# K13-01.net
KiCad netlist of a schematic drawn in Altium Designer
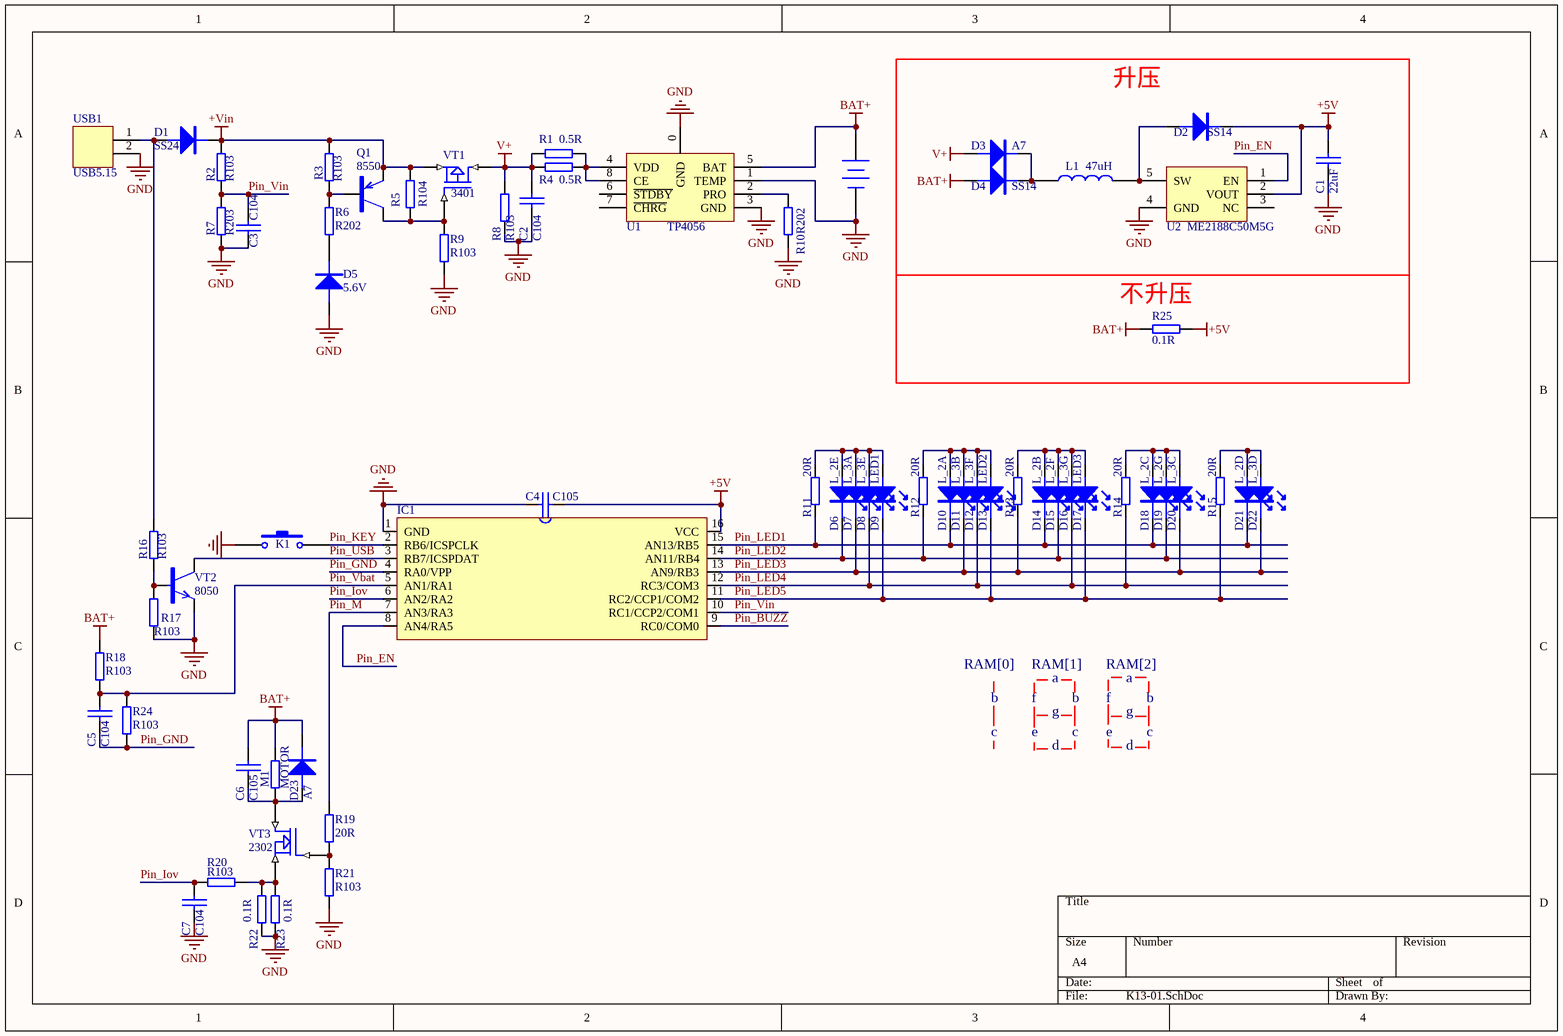
[diagram p0: K13-01.SchDoc]

(export (version "E")
  (design (tool "Eeschema 10.0.6"))
  (components
    (comp (ref "BT1")
      (value "Battery")
      (footprint "BAT")
      (fields (field (name "PUBLISHER") "Altium Limited"))
      (libsource (lib "altium-import") (part "root_3_Battery_"))
    )
    (comp (ref "C1") (value "22uF") (footprint "1206") (libsource (lib "altium-import") (part "root_0_CAP_")))
    (comp (ref "C2") (value "C104") (footprint "0603") (libsource (lib "altium-import") (part "root_2_CAP_")))
    (comp (ref "C3") (value "C104") (footprint "0603") (libsource (lib "altium-import") (part "root_2_CAP_")))
    (comp (ref "C4")
      (value "C105")
      (footprint "0805N")
      (libsource (lib "altium-import") (part "root_3_CAP_"))
    )
    (comp (ref "C5") (value "C104") (footprint "0603") (libsource (lib "altium-import") (part "root_2_CAP_")))
    (comp (ref "C6")
      (value "C105")
      (footprint "0805N")
      (libsource (lib "altium-import") (part "root_2_CAP_"))
    )
    (comp (ref "C7") (value "C104") (footprint "0603") (libsource (lib "altium-import") (part "root_2_CAP_")))
    (comp (ref "D1")
      (value "SS24")
      (footprint "DO-214AC")
      (libsource (lib "altium-import") (part "root_0_DIODE_"))
    )
    (comp (ref "D2")
      (value "SS14")
      (footprint "DO-214AC")
      (libsource (lib "altium-import") (part "root_0_DIODE_"))
    )
    (comp (ref "D3")
      (value "A7")
      (footprint "DO-214AC")
      (libsource (lib "altium-import") (part "root_0_DIODE_"))
    )
    (comp (ref "D4")
      (value "SS14")
      (footprint "DO-214AC")
      (libsource (lib "altium-import") (part "root_0_DIODE_"))
    )
    (comp (ref "D5")
      (value "5.6V")
      (footprint "4148")
      (libsource (lib "altium-import") (part "root_1_DIODE_"))
    )
    (comp (ref "D6")
      (value "L_2E")
      (footprint "LED0603")
      (libsource (lib "altium-import") (part "root_3_LED_"))
    )
    (comp (ref "D7")
      (value "L_3A")
      (footprint "LED0603")
      (libsource (lib "altium-import") (part "root_3_LED_"))
    )
    (comp (ref "D8")
      (value "L_3E")
      (footprint "LED0603")
      (libsource (lib "altium-import") (part "root_3_LED_"))
    )
    (comp (ref "D9")
      (value "LED1")
      (footprint "LED0603")
      (libsource (lib "altium-import") (part "root_3_LED_"))
    )
    (comp (ref "D10")
      (value "L_2A")
      (footprint "LED0603")
      (libsource (lib "altium-import") (part "root_3_LED_"))
    )
    (comp (ref "D11")
      (value "L_3B")
      (footprint "LED0603")
      (libsource (lib "altium-import") (part "root_3_LED_"))
    )
    (comp (ref "D12")
      (value "L_3F")
      (footprint "LED0603")
      (libsource (lib "altium-import") (part "root_3_LED_"))
    )
    (comp (ref "D13")
      (value "LED2")
      (footprint "LED0603")
      (libsource (lib "altium-import") (part "root_3_LED_"))
    )
    (comp (ref "D14")
      (value "L_2B")
      (footprint "LED0603")
      (libsource (lib "altium-import") (part "root_3_LED_"))
    )
    (comp (ref "D15")
      (value "L_2F")
      (footprint "LED0603")
      (libsource (lib "altium-import") (part "root_3_LED_"))
    )
    (comp (ref "D16")
      (value "L_3G")
      (footprint "LED0603")
      (libsource (lib "altium-import") (part "root_3_LED_"))
    )
    (comp (ref "D17")
      (value "LED3")
      (footprint "LED0603")
      (libsource (lib "altium-import") (part "root_3_LED_"))
    )
    (comp (ref "D18")
      (value "L_2C")
      (footprint "LED0603")
      (libsource (lib "altium-import") (part "root_3_LED_"))
    )
    (comp (ref "D19")
      (value "L_2G")
      (footprint "LED0603")
      (libsource (lib "altium-import") (part "root_3_LED_"))
    )
    (comp (ref "D20")
      (value "L_3C")
      (footprint "LED0603")
      (libsource (lib "altium-import") (part "root_3_LED_"))
    )
    (comp (ref "D21")
      (value "L_2D")
      (footprint "LED0603")
      (libsource (lib "altium-import") (part "root_3_LED_"))
    )
    (comp (ref "D22")
      (value "L_3D")
      (footprint "LED0603")
      (libsource (lib "altium-import") (part "root_3_LED_"))
    )
    (comp (ref "D23")
      (value "A7")
      (footprint "4148")
      (libsource (lib "altium-import") (part "root_1_mirrored_DIODE_"))
    )
    (comp (ref "IC1") (value "~") (footprint "SOP-16") (libsource (lib "MySCHLib") (part "MCU_1712")))
    (comp (ref "K1")
      (value "SW-PB")
      (footprint "D6_SMT")
      (fields (field (name "PUBLISHER") "Altium Limited"))
      (libsource (lib "altium-import") (part "root_0_SW-PB_"))
    )
    (comp (ref "L1")
      (value "47uH")
      (footprint "CD4X")
      (description "1.5A以上")
      (libsource (lib "YF SCHlib V1.00") (part "L"))
    )
    (comp (ref "M1")
      (value "MOTOR")
      (footprint "bat")
      (libsource (lib "altium-import") (part "root_1_RES2_"))
    )
    (comp (ref "Q1") (value "8550") (footprint "sot-23") (libsource (lib "MySCHLib") (part "8550-SMT")))
    (comp (ref "R1")
      (value "0.5R")
      (footprint "1206")
      (libsource (lib "altium-import") (part "root_0_RES2_"))
    )
    (comp (ref "R2")
      (value "R103")
      (footprint "0603")
      (libsource (lib "altium-import") (part "root_3_RES2_"))
    )
    (comp (ref "R3")
      (value "R103")
      (footprint "0603")
      (libsource (lib "altium-import") (part "root_3_RES2_"))
    )
    (comp (ref "R4")
      (value "0.5R")
      (footprint "1206")
      (libsource (lib "altium-import") (part "root_0_RES2_"))
    )
    (comp (ref "R5")
      (value "R104")
      (footprint "0603")
      (libsource (lib "altium-import") (part "root_1_RES2_"))
    )
    (comp (ref "R6")
      (value "R202")
      (footprint "0603")
      (libsource (lib "altium-import") (part "root_1_RES2_"))
    )
    (comp (ref "R7")
      (value "R203")
      (footprint "0603")
      (libsource (lib "altium-import") (part "root_3_RES2_"))
    )
    (comp (ref "R8")
      (value "R103")
      (footprint "0603")
      (libsource (lib "altium-import") (part "root_3_RES2_"))
    )
    (comp (ref "R9")
      (value "R103")
      (footprint "0603")
      (libsource (lib "altium-import") (part "root_1_RES2_"))
    )
    (comp (ref "R10")
      (value "R202")
      (footprint "0603")
      (libsource (lib "altium-import") (part "root_3_RES2_"))
    )
    (comp (ref "R11")
      (value "20R")
      (footprint "0603")
      (libsource (lib "altium-import") (part "root_1_mirrored_RES2_"))
    )
    (comp (ref "R12")
      (value "20R")
      (footprint "0603")
      (libsource (lib "altium-import") (part "root_1_mirrored_RES2_"))
    )
    (comp (ref "R13")
      (value "20R")
      (footprint "0603")
      (libsource (lib "altium-import") (part "root_3_mirrored_RES2_"))
    )
    (comp (ref "R14")
      (value "20R")
      (footprint "0603")
      (libsource (lib "altium-import") (part "root_1_mirrored_RES2_"))
    )
    (comp (ref "R15")
      (value "20R")
      (footprint "0603")
      (libsource (lib "altium-import") (part "root_1_mirrored_RES2_"))
    )
    (comp (ref "R16")
      (value "R103")
      (footprint "0603")
      (libsource (lib "altium-import") (part "root_1_RES2_"))
    )
    (comp (ref "R17")
      (value "R103")
      (footprint "0603")
      (libsource (lib "altium-import") (part "root_1_RES2_"))
    )
    (comp (ref "R18")
      (value "R103")
      (footprint "0603")
      (libsource (lib "altium-import") (part "root_1_mirrored_RES2_"))
    )
    (comp (ref "R19")
      (value "20R")
      (footprint "0603")
      (libsource (lib "altium-import") (part "root_1_mirrored_RES2_"))
    )
    (comp (ref "R20")
      (value "R103")
      (footprint "0603")
      (libsource (lib "altium-import") (part "root_0_RES2_"))
    )
    (comp (ref "R21")
      (value "R103")
      (footprint "0603")
      (libsource (lib "altium-import") (part "root_3_mirrored_RES2_"))
    )
    (comp (ref "R22")
      (value "0.1R")
      (footprint "1206")
      (libsource (lib "altium-import") (part "root_1_RES2_"))
    )
    (comp (ref "R23")
      (value "0.1R")
      (footprint "1206")
      (libsource (lib "altium-import") (part "root_1_RES2_"))
    )
    (comp (ref "R24")
      (value "R103")
      (footprint "0603")
      (libsource (lib "altium-import") (part "root_3_mirrored_RES2_"))
    )
    (comp (ref "R25")
      (value "0.1R")
      (footprint "1206")
      (libsource (lib "altium-import") (part "root_2_mirrored_RES2_"))
    )
    (comp (ref "U1") (value "TP4056") (footprint "ESOP-8") (libsource (lib "MySCHLib") (part "TP4056")))
    (comp (ref "U2")
      (value "ME2188C50M5G")
      (footprint "SOT-23-5")
      (libsource (lib "MySCHLib") (part "TP5303"))
    )
    (comp (ref "USB1")
      (value "USB5.15")
      (footprint "BAT")
      (libsource (lib "altium-import") (part "root_0_USB2_"))
    )
    (comp (ref "VT1") (value "3401") (footprint "SOT-23") (libsource (lib "MySCHLib") (part "MOSFET P")))
    (comp (ref "VT2") (value "8050") (footprint "SOT-23") (libsource (lib "MySCHLib") (part "8050-SMT")))
    (comp (ref "VT3")
      (value "2302")
      (footprint "sot-23")
      (libsource (lib "altium-import") (part "root_0_mirrored_MOSFET N_"))
    )
  )
  (nets
    (net (code "1") (name "+5V") (class "Default")
      (node (ref "C1") (pin "1") (pinfunction "1_1") (pintype "passive"))
      (node (ref "C4") (pin "1") (pinfunction "1_1") (pintype "passive"))
      (node (ref "D2") (pin "2") (pinfunction "K_2") (pintype "passive"))
      (node (ref "IC1") (pin "16") (pinfunction "VCC_16") (pintype "passive"))
      (node (ref "R25") (pin "2") (pinfunction "2_2") (pintype "passive"))
      (node (ref "U2") (pin "2") (pinfunction "VOUT_2") (pintype "passive"))
    )
    (net (code "2") (name "+Vin") (class "Default")
      (node (ref "D1") (pin "2") (pinfunction "K_2") (pintype "passive"))
      (node (ref "Q1") (pin "2") (pinfunction "E_2") (pintype "passive"))
      (node (ref "R2") (pin "1") (pinfunction "1_1") (pintype "passive"))
      (node (ref "R3") (pin "1") (pinfunction "1_1") (pintype "passive"))
      (node (ref "R5") (pin "2") (pinfunction "2_2") (pintype "passive"))
      (node (ref "VT1") (pin "2") (pinfunction "S_2") (pintype "input"))
    )
    (net (code "3") (name "/Pin_BUZZ") (class "Default")
      (node (ref "IC1") (pin "9") (pinfunction "RC0/COM0_9") (pintype "passive"))
    )
    (net (code "4") (name "/Pin_EN") (class "Default")
      (node (ref "IC1") (pin "8") (pinfunction "AN4/RA5_8") (pintype "passive"))
      (node (ref "U2") (pin "1") (pinfunction "EN_1") (pintype "passive"))
    )
    (net (code "5") (name "/Pin_GND") (class "Default")
      (node (ref "C5") (pin "1") (pinfunction "1_1") (pintype "passive"))
      (node (ref "IC1") (pin "4") (pinfunction "RA0/VPP_4") (pintype "passive"))
      (node (ref "R24") (pin "2") (pinfunction "2_2") (pintype "passive"))
    )
    (net (code "6") (name "/Pin_Iov") (class "Default")
      (node (ref "C7") (pin "2") (pinfunction "2_2") (pintype "passive"))
      (node (ref "IC1") (pin "6") (pinfunction "AN2/RA2_6") (pintype "passive"))
      (node (ref "R20") (pin "1") (pinfunction "1_1") (pintype "passive"))
    )
    (net (code "7") (name "/Pin_KEY") (class "Default")
      (node (ref "IC1") (pin "2") (pinfunction "RB6/ICSPCLK_2") (pintype "passive"))
      (node (ref "K1") (pin "2") (pinfunction "2_2") (pintype "passive"))
    )
    (net (code "8") (name "/Pin_LED1") (class "Default")
      (node (ref "D10") (pin "2") (pinfunction "2_2") (pintype "passive"))
      (node (ref "D14") (pin "2") (pinfunction "2_2") (pintype "passive"))
      (node (ref "D18") (pin "2") (pinfunction "2_2") (pintype "passive"))
      (node (ref "D21") (pin "2") (pinfunction "2_2") (pintype "passive"))
      (node (ref "IC1") (pin "15") (pinfunction "AN13/RB5_15") (pintype "passive"))
      (node (ref "R11") (pin "1") (pinfunction "1_1") (pintype "passive"))
    )
    (net (code "9") (name "/Pin_LED2") (class "Default")
      (node (ref "D15") (pin "2") (pinfunction "2_2") (pintype "passive"))
      (node (ref "D19") (pin "2") (pinfunction "2_2") (pintype "passive"))
      (node (ref "D6") (pin "2") (pinfunction "2_2") (pintype "passive"))
      (node (ref "IC1") (pin "14") (pinfunction "AN11/RB4_14") (pintype "passive"))
      (node (ref "R12") (pin "1") (pinfunction "1_1") (pintype "passive"))
    )
    (net (code "10") (name "/Pin_LED3") (class "Default")
      (node (ref "D11") (pin "2") (pinfunction "2_2") (pintype "passive"))
      (node (ref "D20") (pin "2") (pinfunction "2_2") (pintype "passive"))
      (node (ref "D22") (pin "2") (pinfunction "2_2") (pintype "passive"))
      (node (ref "D7") (pin "2") (pinfunction "2_2") (pintype "passive"))
      (node (ref "IC1") (pin "13") (pinfunction "AN9/RB3_13") (pintype "passive"))
      (node (ref "R13") (pin "2") (pinfunction "2_2") (pintype "passive"))
    )
    (net (code "11") (name "/Pin_LED4") (class "Default")
      (node (ref "D12") (pin "2") (pinfunction "2_2") (pintype "passive"))
      (node (ref "D16") (pin "2") (pinfunction "2_2") (pintype "passive"))
      (node (ref "D8") (pin "2") (pinfunction "2_2") (pintype "passive"))
      (node (ref "IC1") (pin "12") (pinfunction "RC3/COM3_12") (pintype "passive"))
      (node (ref "R14") (pin "1") (pinfunction "1_1") (pintype "passive"))
    )
    (net (code "12") (name "/Pin_LED5") (class "Default")
      (node (ref "D13") (pin "2") (pinfunction "2_2") (pintype "passive"))
      (node (ref "D17") (pin "2") (pinfunction "2_2") (pintype "passive"))
      (node (ref "D9") (pin "2") (pinfunction "2_2") (pintype "passive"))
      (node (ref "IC1") (pin "11") (pinfunction "RC2/CCP1/COM2_11") (pintype "passive"))
      (node (ref "R15") (pin "1") (pinfunction "1_1") (pintype "passive"))
    )
    (net (code "13") (name "/Pin_M") (class "Default")
      (node (ref "IC1") (pin "7") (pinfunction "AN3/RA3_7") (pintype "passive"))
      (node (ref "R19") (pin "2") (pinfunction "2_2") (pintype "passive"))
    )
    (net (code "14") (name "/Pin_USB") (class "Default")
      (node (ref "IC1") (pin "3") (pinfunction "RB7/ICSPDAT_3") (pintype "passive"))
      (node (ref "VT2") (pin "3") (pinfunction "C_3") (pintype "passive"))
    )
    (net (code "15") (name "/Pin_Vbat") (class "Default")
      (node (ref "C5") (pin "2") (pinfunction "2_2") (pintype "passive"))
      (node (ref "IC1") (pin "5") (pinfunction "AN1/RA1_5") (pintype "passive"))
      (node (ref "R18") (pin "1") (pinfunction "1_1") (pintype "passive"))
      (node (ref "R24") (pin "1") (pinfunction "1_1") (pintype "passive"))
    )
    (net (code "16") (name "/Pin_Vin") (class "Default")
      (node (ref "C3") (pin "2") (pinfunction "2_2") (pintype "passive"))
      (node (ref "IC1") (pin "10") (pinfunction "RC1/CCP2/COM1_10") (pintype "passive"))
      (node (ref "R2") (pin "2") (pinfunction "2_2") (pintype "passive"))
      (node (ref "R7") (pin "1") (pinfunction "1_1") (pintype "passive"))
    )
    (net (code "17") (name "BAT+") (class "Default")
      (node (ref "BT1") (pin "1") (pinfunction "+_1") (pintype "passive"))
      (node (ref "C6") (pin "2") (pinfunction "2_2") (pintype "passive"))
      (node (ref "D23") (pin "2") (pinfunction "K_2") (pintype "passive"))
      (node (ref "D4") (pin "1") (pinfunction "A_1") (pintype "passive"))
      (node (ref "M1") (pin "2") (pinfunction "2_2") (pintype "passive"))
      (node (ref "R18") (pin "2") (pinfunction "2_2") (pintype "passive"))
      (node (ref "R25") (pin "1") (pinfunction "1_1") (pintype "passive"))
      (node (ref "U1") (pin "5") (pinfunction "BAT_5") (pintype "passive"))
    )
    (net (code "18") (name "GND") (class "Default")
      (node (ref "BT1") (pin "2") (pinfunction "-_2") (pintype "passive"))
      (node (ref "C1") (pin "2") (pinfunction "2_2") (pintype "passive"))
      (node (ref "C2") (pin "1") (pinfunction "1_1") (pintype "passive"))
      (node (ref "C3") (pin "1") (pinfunction "1_1") (pintype "passive"))
      (node (ref "C4") (pin "2") (pinfunction "2_2") (pintype "passive"))
      (node (ref "C7") (pin "1") (pinfunction "1_1") (pintype "passive"))
      (node (ref "D5") (pin "1") (pinfunction "A_1") (pintype "passive"))
      (node (ref "IC1") (pin "1") (pinfunction "GND_1") (pintype "passive"))
      (node (ref "K1") (pin "1") (pinfunction "1_1") (pintype "passive"))
      (node (ref "R10") (pin "2") (pinfunction "2_2") (pintype "passive"))
      (node (ref "R17") (pin "1") (pinfunction "1_1") (pintype "passive"))
      (node (ref "R21") (pin "2") (pinfunction "2_2") (pintype "passive"))
      (node (ref "R22") (pin "1") (pinfunction "1_1") (pintype "passive"))
      (node (ref "R23") (pin "1") (pinfunction "1_1") (pintype "passive"))
      (node (ref "R7") (pin "2") (pinfunction "2_2") (pintype "passive"))
      (node (ref "R8") (pin "2") (pinfunction "2_2") (pintype "passive"))
      (node (ref "R9") (pin "1") (pinfunction "1_1") (pintype "passive"))
      (node (ref "U1") (pin "0") (pinfunction "GND_0") (pintype "passive"))
      (node (ref "U1") (pin "1") (pinfunction "TEMP_1") (pintype "passive"))
      (node (ref "U1") (pin "3") (pinfunction "GND_3") (pintype "passive"))
      (node (ref "U2") (pin "4") (pinfunction "GND_4") (pintype "passive"))
      (node (ref "USB1") (pin "2") (pinfunction "2_2") (pintype "passive"))
      (node (ref "VT2") (pin "2") (pinfunction "E_2") (pintype "passive"))
    )
    (net (code "19") (name "Net-(D1-A)") (class "Default")
      (node (ref "D1") (pin "1") (pinfunction "A_1") (pintype "passive"))
      (node (ref "R16") (pin "2") (pinfunction "2_2") (pintype "passive"))
      (node (ref "USB1") (pin "1") (pinfunction "1_1") (pintype "passive"))
    )
    (net (code "20") (name "Net-(D2-A)") (class "Default")
      (node (ref "D2") (pin "1") (pinfunction "A_1") (pintype "passive"))
      (node (ref "L1") (pin "2") (pinfunction "2_2") (pintype "passive"))
      (node (ref "U2") (pin "5") (pinfunction "SW_5") (pintype "passive"))
    )
    (net (code "21") (name "Net-(D3-K)") (class "Default")
      (node (ref "D3") (pin "2") (pinfunction "K_2") (pintype "passive"))
      (node (ref "D4") (pin "2") (pinfunction "K_2") (pintype "passive"))
      (node (ref "L1") (pin "1") (pinfunction "1_1") (pintype "passive"))
    )
    (net (code "22") (name "Net-(D5-K)") (class "Default")
      (node (ref "D5") (pin "2") (pinfunction "K_2") (pintype "passive"))
      (node (ref "R6") (pin "1") (pinfunction "1_1") (pintype "passive"))
    )
    (net (code "23") (name "Net-(D6-Pad1)") (class "Default")
      (node (ref "D6") (pin "1") (pinfunction "1_1") (pintype "passive"))
      (node (ref "D7") (pin "1") (pinfunction "1_1") (pintype "passive"))
      (node (ref "D8") (pin "1") (pinfunction "1_1") (pintype "passive"))
      (node (ref "D9") (pin "1") (pinfunction "1_1") (pintype "passive"))
      (node (ref "R11") (pin "2") (pinfunction "2_2") (pintype "passive"))
    )
    (net (code "24") (name "Net-(D10-Pad1)") (class "Default")
      (node (ref "D10") (pin "1") (pinfunction "1_1") (pintype "passive"))
      (node (ref "D11") (pin "1") (pinfunction "1_1") (pintype "passive"))
      (node (ref "D12") (pin "1") (pinfunction "1_1") (pintype "passive"))
      (node (ref "D13") (pin "1") (pinfunction "1_1") (pintype "passive"))
      (node (ref "R12") (pin "2") (pinfunction "2_2") (pintype "passive"))
    )
    (net (code "25") (name "Net-(D14-Pad1)") (class "Default")
      (node (ref "D14") (pin "1") (pinfunction "1_1") (pintype "passive"))
      (node (ref "D15") (pin "1") (pinfunction "1_1") (pintype "passive"))
      (node (ref "D16") (pin "1") (pinfunction "1_1") (pintype "passive"))
      (node (ref "D17") (pin "1") (pinfunction "1_1") (pintype "passive"))
      (node (ref "R13") (pin "1") (pinfunction "1_1") (pintype "passive"))
    )
    (net (code "26") (name "Net-(D18-Pad1)") (class "Default")
      (node (ref "D18") (pin "1") (pinfunction "1_1") (pintype "passive"))
      (node (ref "D19") (pin "1") (pinfunction "1_1") (pintype "passive"))
      (node (ref "D20") (pin "1") (pinfunction "1_1") (pintype "passive"))
      (node (ref "R14") (pin "2") (pinfunction "2_2") (pintype "passive"))
    )
    (net (code "27") (name "Net-(D21-Pad1)") (class "Default")
      (node (ref "D21") (pin "1") (pinfunction "1_1") (pintype "passive"))
      (node (ref "D22") (pin "1") (pinfunction "1_1") (pintype "passive"))
      (node (ref "R15") (pin "2") (pinfunction "2_2") (pintype "passive"))
    )
    (net (code "28") (name "Net-(D23-A)") (class "Default")
      (node (ref "C6") (pin "1") (pinfunction "1_1") (pintype "passive"))
      (node (ref "D23") (pin "1") (pinfunction "A_1") (pintype "passive"))
      (node (ref "M1") (pin "1") (pinfunction "1_1") (pintype "passive"))
      (node (ref "VT3") (pin "3") (pinfunction "D_3") (pintype "input"))
    )
    (net (code "29") (name "Net-(Q1-B)") (class "Default")
      (node (ref "Q1") (pin "1") (pinfunction "B_1") (pintype "passive"))
      (node (ref "R3") (pin "2") (pinfunction "2_2") (pintype "passive"))
      (node (ref "R6") (pin "2") (pinfunction "2_2") (pintype "passive"))
    )
    (net (code "30") (name "Net-(Q1-C)") (class "Default")
      (node (ref "Q1") (pin "3") (pinfunction "C_3") (pintype "passive"))
      (node (ref "R5") (pin "1") (pinfunction "1_1") (pintype "passive"))
      (node (ref "R9") (pin "2") (pinfunction "2_2") (pintype "passive"))
      (node (ref "VT1") (pin "1") (pinfunction "G_1") (pintype "input"))
    )
    (net (code "31") (name "Net-(U1-CE)") (class "Default")
      (node (ref "R1") (pin "2") (pinfunction "2_2") (pintype "passive"))
      (node (ref "R4") (pin "2") (pinfunction "2_2") (pintype "passive"))
      (node (ref "U1") (pin "4") (pinfunction "VDD_4") (pintype "passive"))
      (node (ref "U1") (pin "8") (pinfunction "CE_8") (pintype "passive"))
    )
    (net (code "32") (name "Net-(U1-PRO)") (class "Default")
      (node (ref "R10") (pin "1") (pinfunction "1_1") (pintype "passive"))
      (node (ref "U1") (pin "2") (pinfunction "PRO_2") (pintype "passive"))
    )
    (net (code "33") (name "Net-(VT2-B)") (class "Default")
      (node (ref "R16") (pin "1") (pinfunction "1_1") (pintype "passive"))
      (node (ref "R17") (pin "2") (pinfunction "2_2") (pintype "passive"))
      (node (ref "VT2") (pin "1") (pinfunction "B_1") (pintype "passive"))
    )
    (net (code "34") (name "Net-(VT3-G)") (class "Default")
      (node (ref "R19") (pin "1") (pinfunction "1_1") (pintype "passive"))
      (node (ref "R21") (pin "1") (pinfunction "1_1") (pintype "passive"))
      (node (ref "VT3") (pin "1") (pinfunction "G_1") (pintype "input"))
    )
    (net (code "35") (name "Net-(VT3-S)") (class "Default")
      (node (ref "R20") (pin "2") (pinfunction "2_2") (pintype "passive"))
      (node (ref "R22") (pin "2") (pinfunction "2_2") (pintype "passive"))
      (node (ref "R23") (pin "2") (pinfunction "2_2") (pintype "passive"))
      (node (ref "VT3") (pin "2") (pinfunction "S_2") (pintype "input"))
    )
    (net (code "36") (name "V+") (class "Default")
      (node (ref "C2") (pin "2") (pinfunction "2_2") (pintype "passive"))
      (node (ref "D3") (pin "1") (pinfunction "A_1") (pintype "passive"))
      (node (ref "R1") (pin "1") (pinfunction "1_1") (pintype "passive"))
      (node (ref "R4") (pin "1") (pinfunction "1_1") (pintype "passive"))
      (node (ref "R8") (pin "1") (pinfunction "1_1") (pintype "passive"))
      (node (ref "VT1") (pin "3") (pinfunction "D_3") (pintype "input"))
    )
    (net (code "37") (name "unconnected-(U1-~{CHRG}-Pad7)") (class "Default")
      (node (ref "U1") (pin "7") (pinfunction "~{CHRG}_7") (pintype "passive"))
    )
    (net (code "38") (name "unconnected-(U1-~{STDBY}-Pad6)") (class "Default")
      (node (ref "U1") (pin "6") (pinfunction "~{STDBY}_6") (pintype "passive"))
    )
    (net (code "39") (name "unconnected-(U2-NC-Pad3)") (class "Default")
      (node (ref "U2") (pin "3") (pinfunction "NC_3") (pintype "passive"))
    )
  )
)
